# PartB.net
KiCad netlist of a schematic drawn in Altium Designer
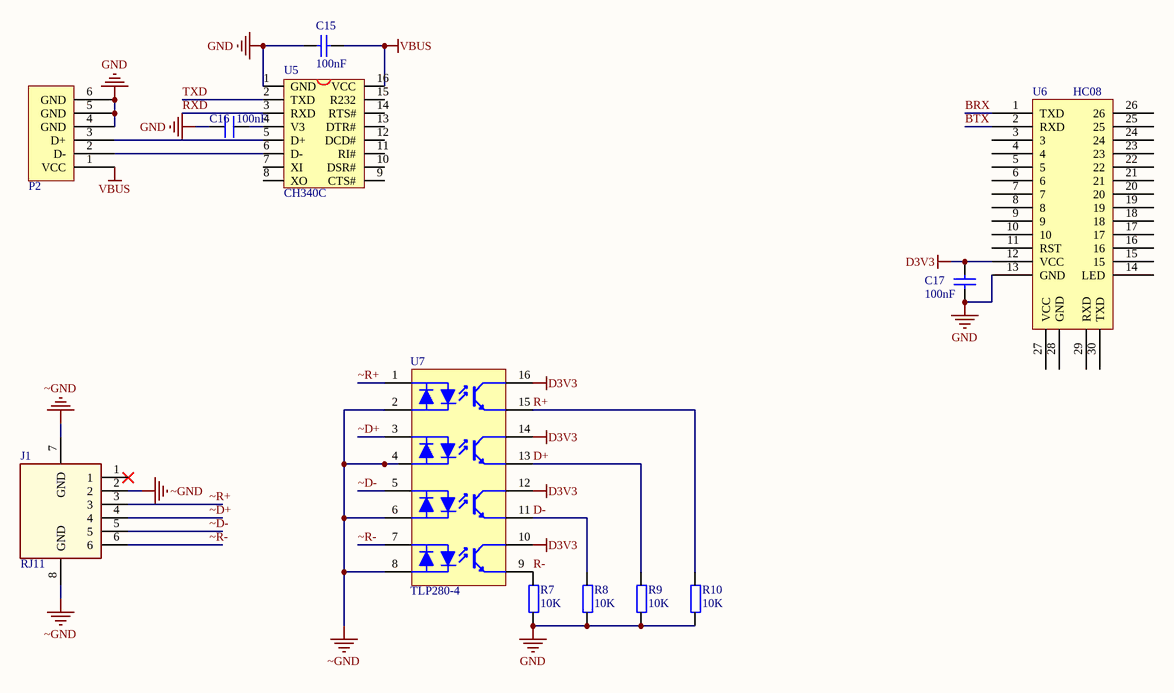
[diagram p0: PartB.SchDoc]

(export (version "E")
  (design (tool "Eeschema 10.0.6"))
  (components
    (comp (ref "C15")
      (value "100nF")
      (footprint "0603C")
      (description "Capacitor")
      (fields (field (name "PUBLISHER") "Altium Limited"))
      (libsource (lib "Crazy_PCB") (part "Cap"))
    )
    (comp (ref "C16")
      (value "100nF")
      (footprint "0603C")
      (libsource (lib "WarShip V3 STM32103封装库") (part "C"))
    )
    (comp (ref "C17")
      (value "100nF")
      (footprint "0603C")
      (description "Capacitor")
      (fields (field (name "PUBLISHER") "Altium Limited"))
      (libsource (lib "Crazy_PCB") (part "=value"))
    )
    (comp (ref "J1") (value "RJ11") (footprint "RJ11") (libsource (lib "JL_SCH") (part "RJ11")))
    (comp (ref "P2") (value "USB-B") (footprint "USB-B") (libsource (lib "DX") (part "USB-B")))
    (comp (ref "R7") (value "10K") (footprint "0603R") (libsource (lib "WarShip V3 STM32103封装库") (part "R")))
    (comp (ref "R8") (value "10K") (footprint "0603R") (libsource (lib "WarShip V3 STM32103封装库") (part "R")))
    (comp (ref "R9") (value "10K") (footprint "0603R") (libsource (lib "WarShip V3 STM32103封装库") (part "R")))
    (comp (ref "R10") (value "10K") (footprint "0603R") (libsource (lib "WarShip V3 STM32103封装库") (part "R")))
    (comp (ref "U5")
      (value "CH340C")
      (footprint "SO-16")
      (description "USB2UART")
      (libsource (lib "WarShip V3 STM32103封装库") (part "CH340G"))
    )
    (comp (ref "U6") (value "HC08") (footprint "HC-05/06/08V15") (libsource (lib "SS") (part "HC08")))
    (comp (ref "U7")
      (value "TLP280-4")
      (footprint "SOP16N_L")
      (description "4组光耦")
      (fields (field (name "版权归属") "源创客"))
      (libsource (lib "11.1 - 传感元件") (part "TLP280-4"))
    )
  )
  (nets
    (net (code "1") (name "/BRX") (class "Default")
      (node (ref "U6") (pin "1") (pinfunction "TXD_1") (pintype "passive"))
    )
    (net (code "2") (name "/BTX") (class "Default")
      (node (ref "U6") (pin "2") (pinfunction "RXD_2") (pintype "passive"))
    )
    (net (code "3") (name "/D+") (class "Default")
      (node (ref "R9") (pin "2") (pintype "passive"))
      (node (ref "U7") (pin "13") (pinfunction "13_13") (pintype "passive"))
    )
    (net (code "4") (name "/D-") (class "Default")
      (node (ref "R8") (pin "2") (pintype "passive"))
      (node (ref "U7") (pin "11") (pinfunction "11_11") (pintype "passive"))
    )
    (net (code "5") (name "/R+") (class "Default")
      (node (ref "R10") (pin "2") (pintype "passive"))
      (node (ref "U7") (pin "15") (pinfunction "15_15") (pintype "passive"))
    )
    (net (code "6") (name "/R-") (class "Default")
      (node (ref "R7") (pin "2") (pintype "passive"))
      (node (ref "U7") (pin "9") (pinfunction "9_9") (pintype "passive"))
    )
    (net (code "7") (name "/RXD") (class "Default")
      (node (ref "U5") (pin "3") (pinfunction "RXD_3") (pintype "passive"))
    )
    (net (code "8") (name "/TXD") (class "Default")
      (node (ref "U5") (pin "2") (pinfunction "TXD_2") (pintype "passive"))
    )
    (net (code "9") (name "/~D+") (class "Default")
      (node (ref "J1") (pin "4") (pinfunction "4_4") (pintype "passive"))
      (node (ref "U7") (pin "3") (pinfunction "E_3") (pintype "passive"))
    )
    (net (code "10") (name "/~D-") (class "Default")
      (node (ref "J1") (pin "5") (pinfunction "5_5") (pintype "passive"))
      (node (ref "U7") (pin "5") (pinfunction "5_5") (pintype "passive"))
    )
    (net (code "11") (name "/~R+") (class "Default")
      (node (ref "J1") (pin "3") (pinfunction "3_3") (pintype "passive"))
      (node (ref "U7") (pin "1") (pinfunction "A_1") (pintype "passive"))
    )
    (net (code "12") (name "/~R-") (class "Default")
      (node (ref "J1") (pin "6") (pinfunction "6_6") (pintype "passive"))
      (node (ref "U7") (pin "7") (pinfunction "7_7") (pintype "passive"))
    )
    (net (code "13") (name "D3V3") (class "Default")
      (node (ref "C17") (pin "2") (pinfunction "2_2") (pintype "passive"))
      (node (ref "U6") (pin "12") (pinfunction "VCC_12") (pintype "passive"))
      (node (ref "U7") (pin "10") (pinfunction "10_10") (pintype "passive"))
      (node (ref "U7") (pin "12") (pinfunction "12_12") (pintype "passive"))
      (node (ref "U7") (pin "14") (pinfunction "14_14") (pintype "passive"))
      (node (ref "U7") (pin "16") (pinfunction "16_16") (pintype "passive"))
    )
    (net (code "14") (name "GND") (class "Default")
      (node (ref "C15") (pin "1") (pinfunction "1_1") (pintype "passive"))
      (node (ref "C16") (pin "1") (pintype "passive"))
      (node (ref "C17") (pin "1") (pinfunction "1_1") (pintype "passive"))
      (node (ref "P2") (pin "4") (pinfunction "GND_4") (pintype "passive"))
      (node (ref "P2") (pin "5") (pinfunction "GND_5") (pintype "passive"))
      (node (ref "P2") (pin "6") (pinfunction "GND_6") (pintype "passive"))
      (node (ref "R10") (pin "1") (pintype "passive"))
      (node (ref "R7") (pin "1") (pintype "passive"))
      (node (ref "R8") (pin "1") (pintype "passive"))
      (node (ref "R9") (pin "1") (pintype "passive"))
      (node (ref "U5") (pin "1") (pinfunction "GND_1") (pintype "passive"))
      (node (ref "U6") (pin "13") (pinfunction "GND_13") (pintype "passive"))
    )
    (net (code "15") (name "Net-(P2-D+)") (class "Default")
      (node (ref "P2") (pin "3") (pinfunction "D+_3") (pintype "passive"))
      (node (ref "U5") (pin "5") (pinfunction "D+_5") (pintype "passive"))
    )
    (net (code "16") (name "Net-(P2-D-)") (class "Default")
      (node (ref "P2") (pin "2") (pinfunction "D-_2") (pintype "passive"))
      (node (ref "U5") (pin "6") (pinfunction "D-_6") (pintype "passive"))
    )
    (net (code "17") (name "Net-(U5-V3)") (class "Default")
      (node (ref "C16") (pin "2") (pintype "passive"))
      (node (ref "U5") (pin "4") (pinfunction "V3_4") (pintype "passive"))
    )
    (net (code "18") (name "VBUS") (class "Default")
      (node (ref "C15") (pin "2") (pinfunction "2_2") (pintype "passive"))
      (node (ref "P2") (pin "1") (pinfunction "VCC_1") (pintype "passive"))
      (node (ref "U5") (pin "16") (pinfunction "VCC_16") (pintype "passive"))
    )
    (net (code "19") (name "unconnected-(J1-Pad1)") (class "Default")
      (node (ref "J1") (pin "1") (pinfunction "1_1") (pintype "passive+no_connect"))
    )
    (net (code "20") (name "unconnected-(J1-Pad9)") (class "Default")
      (node (ref "J1") (pin "9") (pinfunction "9_9") (pintype "passive"))
    )
    (net (code "21") (name "unconnected-(J1-Pad10)") (class "Default")
      (node (ref "J1") (pin "10") (pinfunction "10_10") (pintype "passive"))
    )
    (net (code "22") (name "unconnected-(U5-CTS#-Pad9)") (class "Default")
      (node (ref "U5") (pin "9") (pinfunction "CTS#_9") (pintype "passive"))
    )
    (net (code "23") (name "unconnected-(U5-DCD#-Pad12)") (class "Default")
      (node (ref "U5") (pin "12") (pinfunction "DCD#_12") (pintype "passive"))
    )
    (net (code "24") (name "unconnected-(U5-DSR#-Pad10)") (class "Default")
      (node (ref "U5") (pin "10") (pinfunction "DSR#_10") (pintype "passive"))
    )
    (net (code "25") (name "unconnected-(U5-DTR#-Pad13)") (class "Default")
      (node (ref "U5") (pin "13") (pinfunction "DTR#_13") (pintype "passive"))
    )
    (net (code "26") (name "unconnected-(U5-R232-Pad15)") (class "Default")
      (node (ref "U5") (pin "15") (pinfunction "R232_15") (pintype "passive"))
    )
    (net (code "27") (name "unconnected-(U5-RI#-Pad11)") (class "Default")
      (node (ref "U5") (pin "11") (pinfunction "RI#_11") (pintype "passive"))
    )
    (net (code "28") (name "unconnected-(U5-RTS#-Pad14)") (class "Default")
      (node (ref "U5") (pin "14") (pinfunction "RTS#_14") (pintype "passive"))
    )
    (net (code "29") (name "unconnected-(U5-XI-Pad7)") (class "Default")
      (node (ref "U5") (pin "7") (pinfunction "XI_7") (pintype "passive"))
    )
    (net (code "30") (name "unconnected-(U5-XO-Pad8)") (class "Default")
      (node (ref "U5") (pin "8") (pinfunction "XO_8") (pintype "passive"))
    )
    (net (code "31") (name "unconnected-(U6-GND-Pad28)") (class "Default")
      (node (ref "U6") (pin "28") (pinfunction "GND_28") (pintype "passive"))
    )
    (net (code "32") (name "unconnected-(U6-LED-Pad14)") (class "Default")
      (node (ref "U6") (pin "14") (pinfunction "LED_14") (pintype "passive"))
    )
    (net (code "33") (name "unconnected-(U6-Pad3)") (class "Default")
      (node (ref "U6") (pin "3") (pinfunction "3_3") (pintype "passive"))
    )
    (net (code "34") (name "unconnected-(U6-Pad4)") (class "Default")
      (node (ref "U6") (pin "4") (pinfunction "4_4") (pintype "passive"))
    )
    (net (code "35") (name "unconnected-(U6-Pad5)") (class "Default")
      (node (ref "U6") (pin "5") (pinfunction "5_5") (pintype "passive"))
    )
    (net (code "36") (name "unconnected-(U6-Pad6)") (class "Default")
      (node (ref "U6") (pin "6") (pinfunction "6_6") (pintype "passive"))
    )
    (net (code "37") (name "unconnected-(U6-Pad7)") (class "Default")
      (node (ref "U6") (pin "7") (pinfunction "7_7") (pintype "passive"))
    )
    (net (code "38") (name "unconnected-(U6-Pad8)") (class "Default")
      (node (ref "U6") (pin "8") (pinfunction "8_8") (pintype "passive"))
    )
    (net (code "39") (name "unconnected-(U6-Pad9)") (class "Default")
      (node (ref "U6") (pin "9") (pinfunction "9_9") (pintype "passive"))
    )
    (net (code "40") (name "unconnected-(U6-Pad10)") (class "Default")
      (node (ref "U6") (pin "10") (pinfunction "10_10") (pintype "passive"))
    )
    (net (code "41") (name "unconnected-(U6-Pad15)") (class "Default")
      (node (ref "U6") (pin "15") (pinfunction "15_15") (pintype "passive"))
    )
    (net (code "42") (name "unconnected-(U6-Pad16)") (class "Default")
      (node (ref "U6") (pin "16") (pinfunction "16_16") (pintype "passive"))
    )
    (net (code "43") (name "unconnected-(U6-Pad17)") (class "Default")
      (node (ref "U6") (pin "17") (pinfunction "17_17") (pintype "passive"))
    )
    (net (code "44") (name "unconnected-(U6-Pad18)") (class "Default")
      (node (ref "U6") (pin "18") (pinfunction "18_18") (pintype "passive"))
    )
    (net (code "45") (name "unconnected-(U6-Pad19)") (class "Default")
      (node (ref "U6") (pin "19") (pinfunction "19_19") (pintype "passive"))
    )
    (net (code "46") (name "unconnected-(U6-Pad20)") (class "Default")
      (node (ref "U6") (pin "20") (pinfunction "20_20") (pintype "passive"))
    )
    (net (code "47") (name "unconnected-(U6-Pad21)") (class "Default")
      (node (ref "U6") (pin "21") (pinfunction "21_21") (pintype "passive"))
    )
    (net (code "48") (name "unconnected-(U6-Pad22)") (class "Default")
      (node (ref "U6") (pin "22") (pinfunction "22_22") (pintype "passive"))
    )
    (net (code "49") (name "unconnected-(U6-Pad23)") (class "Default")
      (node (ref "U6") (pin "23") (pinfunction "23_23") (pintype "passive"))
    )
    (net (code "50") (name "unconnected-(U6-Pad24)") (class "Default")
      (node (ref "U6") (pin "24") (pinfunction "24_24") (pintype "passive"))
    )
    (net (code "51") (name "unconnected-(U6-Pad25)") (class "Default")
      (node (ref "U6") (pin "25") (pinfunction "25_25") (pintype "passive"))
    )
    (net (code "52") (name "unconnected-(U6-Pad26)") (class "Default")
      (node (ref "U6") (pin "26") (pinfunction "26_26") (pintype "passive"))
    )
    (net (code "53") (name "unconnected-(U6-RST-Pad11)") (class "Default")
      (node (ref "U6") (pin "11") (pinfunction "RST_11") (pintype "passive"))
    )
    (net (code "54") (name "unconnected-(U6-RXD-Pad29)") (class "Default")
      (node (ref "U6") (pin "29") (pinfunction "RXD_29") (pintype "passive"))
    )
    (net (code "55") (name "unconnected-(U6-TXD-Pad30)") (class "Default")
      (node (ref "U6") (pin "30") (pinfunction "TXD_30") (pintype "passive"))
    )
    (net (code "56") (name "unconnected-(U6-VCC-Pad27)") (class "Default")
      (node (ref "U6") (pin "27") (pinfunction "VCC_27") (pintype "passive"))
    )
    (net (code "57") (name "~GND") (class "Default")
      (node (ref "J1") (pin "2") (pinfunction "2_2") (pintype "passive"))
      (node (ref "J1") (pin "7") (pinfunction "GND_7") (pintype "passive"))
      (node (ref "J1") (pin "8") (pinfunction "GND_8") (pintype "passive"))
      (node (ref "U7") (pin "2") (pinfunction "K_2") (pintype "passive"))
      (node (ref "U7") (pin "4") (pinfunction "C_4") (pintype "passive"))
      (node (ref "U7") (pin "6") (pinfunction "6_6") (pintype "passive"))
      (node (ref "U7") (pin "8") (pinfunction "8_8") (pintype "passive"))
    )
  )
)
